# main.net
KiCad netlist of a schematic drawn in EAGLE
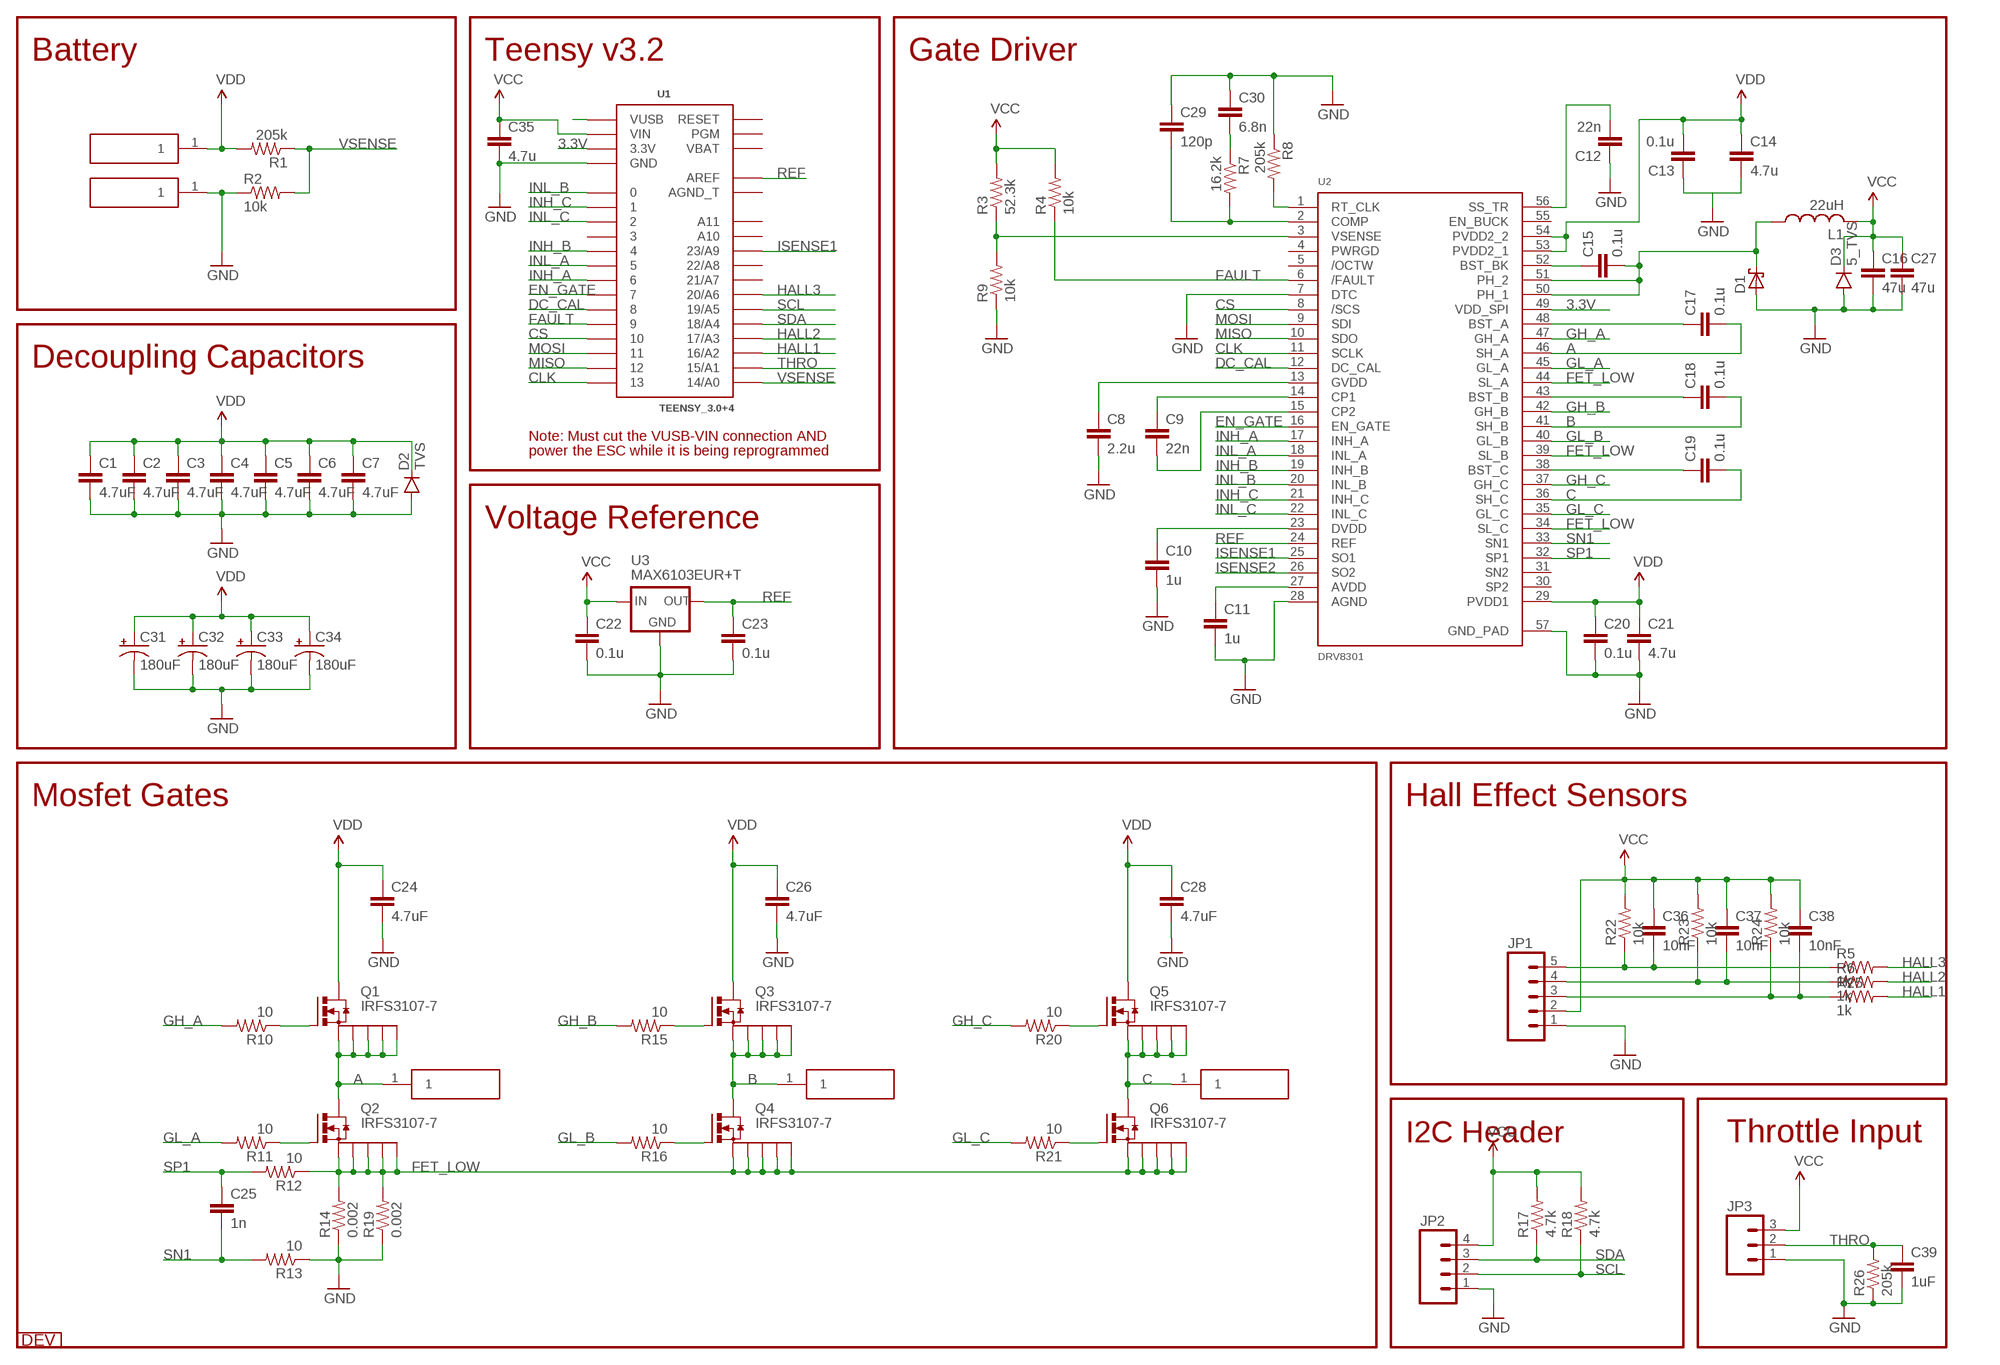
[diagram p0: schematic, sheet 1]

(export (version "E")
  (design (tool "Eeschema 10.0.6"))
  (components
    (comp (ref "C1")
      (value "4.7uF")
      (footprint "eagle-import:1206")
      (libsource (lib "eagle-import") (part "CAP1206"))
    )
    (comp (ref "C2")
      (value "4.7uF")
      (footprint "eagle-import:1206")
      (libsource (lib "eagle-import") (part "CAP1206"))
    )
    (comp (ref "C3")
      (value "4.7uF")
      (footprint "eagle-import:1206")
      (libsource (lib "eagle-import") (part "CAP1206"))
    )
    (comp (ref "C4")
      (value "4.7uF")
      (footprint "eagle-import:1206")
      (libsource (lib "eagle-import") (part "CAP1206"))
    )
    (comp (ref "C5")
      (value "4.7uF")
      (footprint "eagle-import:1206")
      (libsource (lib "eagle-import") (part "CAP1206"))
    )
    (comp (ref "C6")
      (value "4.7uF")
      (footprint "eagle-import:1206")
      (libsource (lib "eagle-import") (part "CAP1206"))
    )
    (comp (ref "C7")
      (value "4.7uF")
      (footprint "eagle-import:1206")
      (libsource (lib "eagle-import") (part "CAP1206"))
    )
    (comp (ref "C8")
      (value "2.2u")
      (footprint "eagle-import:0603-CAP")
      (libsource (lib "eagle-import") (part "CAP0603-CAP"))
    )
    (comp (ref "C9")
      (value "22n")
      (footprint "eagle-import:0603-CAP")
      (libsource (lib "eagle-import") (part "CAP0603-CAP"))
    )
    (comp (ref "C10")
      (value "1u")
      (footprint "eagle-import:0603-CAP")
      (libsource (lib "eagle-import") (part "CAP0603-CAP"))
    )
    (comp (ref "C11")
      (value "1u")
      (footprint "eagle-import:0603-CAP")
      (libsource (lib "eagle-import") (part "CAP0603-CAP"))
    )
    (comp (ref "C12")
      (value "22n")
      (footprint "eagle-import:0603-CAP")
      (libsource (lib "eagle-import") (part "CAP0603-CAP"))
    )
    (comp (ref "C13")
      (value "0.1u")
      (footprint "eagle-import:0603-CAP")
      (libsource (lib "eagle-import") (part "CAP0603-CAP"))
    )
    (comp (ref "C14")
      (value "4.7u")
      (footprint "eagle-import:0805")
      (libsource (lib "eagle-import") (part "CAP0805"))
    )
    (comp (ref "C15")
      (value "0.1u")
      (footprint "eagle-import:0603-CAP")
      (libsource (lib "eagle-import") (part "CAP0603-CAP"))
    )
    (comp (ref "C16")
      (value "47u")
      (footprint "eagle-import:0805")
      (libsource (lib "eagle-import") (part "CAP0805"))
    )
    (comp (ref "C17")
      (value "0.1u")
      (footprint "eagle-import:0603-CAP")
      (libsource (lib "eagle-import") (part "CAP0603-CAP"))
    )
    (comp (ref "C18")
      (value "0.1u")
      (footprint "eagle-import:0603-CAP")
      (libsource (lib "eagle-import") (part "CAP0603-CAP"))
    )
    (comp (ref "C19")
      (value "0.1u")
      (footprint "eagle-import:0603-CAP")
      (libsource (lib "eagle-import") (part "CAP0603-CAP"))
    )
    (comp (ref "C20")
      (value "0.1u")
      (footprint "eagle-import:0603-CAP")
      (libsource (lib "eagle-import") (part "CAP0603-CAP"))
    )
    (comp (ref "C21")
      (value "4.7u")
      (footprint "eagle-import:0805")
      (libsource (lib "eagle-import") (part "CAP0805"))
    )
    (comp (ref "C22")
      (value "0.1u")
      (footprint "eagle-import:0603-CAP")
      (libsource (lib "eagle-import") (part "CAP0603-CAP"))
    )
    (comp (ref "C23")
      (value "0.1u")
      (footprint "eagle-import:0603-CAP")
      (libsource (lib "eagle-import") (part "CAP0603-CAP"))
    )
    (comp (ref "C24")
      (value "4.7uF")
      (footprint "eagle-import:1206")
      (libsource (lib "eagle-import") (part "CAP1206"))
    )
    (comp (ref "C25")
      (value "1n")
      (footprint "eagle-import:0603-CAP")
      (libsource (lib "eagle-import") (part "CAP0603-CAP"))
    )
    (comp (ref "C26")
      (value "4.7uF")
      (footprint "eagle-import:1206")
      (libsource (lib "eagle-import") (part "CAP1206"))
    )
    (comp (ref "C27")
      (value "47u")
      (footprint "eagle-import:0805")
      (libsource (lib "eagle-import") (part "CAP0805"))
    )
    (comp (ref "C28")
      (value "4.7uF")
      (footprint "eagle-import:1206")
      (libsource (lib "eagle-import") (part "CAP1206"))
    )
    (comp (ref "C29")
      (value "120p")
      (footprint "eagle-import:0603-CAP")
      (libsource (lib "eagle-import") (part "CAP0603-CAP"))
    )
    (comp (ref "C30")
      (value "6.8n")
      (footprint "eagle-import:0603-CAP")
      (libsource (lib "eagle-import") (part "CAP0603-CAP"))
    )
    (comp (ref "C31")
      (value "180uF")
      (footprint "eagle-import:E3,5-8")
      (libsource (lib "eagle-import") (part "CPOL-USE3.5-8"))
    )
    (comp (ref "C32")
      (value "180uF")
      (footprint "eagle-import:E3,5-8")
      (libsource (lib "eagle-import") (part "CPOL-USE3.5-8"))
    )
    (comp (ref "C33")
      (value "180uF")
      (footprint "eagle-import:E3,5-8")
      (libsource (lib "eagle-import") (part "CPOL-USE3.5-8"))
    )
    (comp (ref "C34")
      (value "180uF")
      (footprint "eagle-import:E3,5-8")
      (libsource (lib "eagle-import") (part "CPOL-USE3.5-8"))
    )
    (comp (ref "C35")
      (value "4.7u")
      (footprint "eagle-import:0603-CAP")
      (libsource (lib "eagle-import") (part "CAP0603-CAP"))
    )
    (comp (ref "C36")
      (value "10nF")
      (footprint "eagle-import:0603-CAP")
      (libsource (lib "eagle-import") (part "SparkFun-Passives_CAP0603-CAP"))
    )
    (comp (ref "C37")
      (value "10nF")
      (footprint "eagle-import:0603-CAP")
      (libsource (lib "eagle-import") (part "SparkFun-Passives_CAP0603-CAP"))
    )
    (comp (ref "C38")
      (value "10nF")
      (footprint "eagle-import:0603-CAP")
      (libsource (lib "eagle-import") (part "SparkFun-Passives_CAP0603-CAP"))
    )
    (comp (ref "C39")
      (value "1uF")
      (footprint "eagle-import:0603-CAP")
      (libsource (lib "eagle-import") (part "SparkFun-Passives_CAP0603-CAP"))
    )
    (comp (ref "D1")
      (value "SCHOTTKY_SMA")
      (footprint "eagle-import:SMA")
      (libsource (lib "eagle-import") (part "SCHOTTKY_SMA"))
    )
    (comp (ref "D2")
      (value "TVS")
      (footprint "eagle-import:SMC")
      (libsource (lib "eagle-import") (part "DIODEES3J"))
    )
    (comp (ref "D3")
      (value "5_TVS")
      (footprint "eagle-import:SOT23-3")
      (libsource (lib "eagle-import") (part "DIODESOT23"))
    )
    (comp (ref "J1")
      (value "0.125_PAD")
      (footprint "eagle-import:0.125_PAD")
      (libsource (lib "eagle-import") (part "0.125_PAD"))
    )
    (comp (ref "J2")
      (value "0.125_PAD")
      (footprint "eagle-import:0.125_PAD")
      (libsource (lib "eagle-import") (part "0.125_PAD"))
    )
    (comp (ref "J3")
      (value "0.125_PAD")
      (footprint "eagle-import:0.125_PAD")
      (libsource (lib "eagle-import") (part "0.125_PAD"))
    )
    (comp (ref "J4")
      (value "0.125_PAD")
      (footprint "eagle-import:0.125_PAD")
      (libsource (lib "eagle-import") (part "0.125_PAD"))
    )
    (comp (ref "J5")
      (value "0.125_PAD")
      (footprint "eagle-import:0.125_PAD")
      (libsource (lib "eagle-import") (part "0.125_PAD"))
    )
    (comp (ref "JP1")
      (value "M05PTH")
      (footprint "eagle-import:1X05")
      (libsource (lib "eagle-import") (part "M05PTH"))
    )
    (comp (ref "JP2")
      (value "M04PTH")
      (footprint "eagle-import:1X04")
      (libsource (lib "eagle-import") (part "M04PTH"))
    )
    (comp (ref "JP3")
      (value "M03PTH")
      (footprint "eagle-import:1X03")
      (libsource (lib "eagle-import") (part "M03PTH"))
    )
    (comp (ref "L1")
      (value "22uH")
      (footprint "eagle-import:L5650M")
      (libsource (lib "eagle-import") (part "L-USL5650M"))
    )
    (comp (ref "Q1")
      (value "IRFS3107-7")
      (footprint "eagle-import:D2PAK-7")
      (libsource (lib "eagle-import") (part "IRFS3107-7"))
    )
    (comp (ref "Q2")
      (value "IRFS3107-7")
      (footprint "eagle-import:D2PAK-7")
      (libsource (lib "eagle-import") (part "IRFS3107-7"))
    )
    (comp (ref "Q3")
      (value "IRFS3107-7")
      (footprint "eagle-import:D2PAK-7")
      (libsource (lib "eagle-import") (part "IRFS3107-7"))
    )
    (comp (ref "Q4")
      (value "IRFS3107-7")
      (footprint "eagle-import:D2PAK-7")
      (libsource (lib "eagle-import") (part "IRFS3107-7"))
    )
    (comp (ref "Q5")
      (value "IRFS3107-7")
      (footprint "eagle-import:D2PAK-7")
      (libsource (lib "eagle-import") (part "IRFS3107-7"))
    )
    (comp (ref "Q6")
      (value "IRFS3107-7")
      (footprint "eagle-import:D2PAK-7")
      (libsource (lib "eagle-import") (part "IRFS3107-7"))
    )
    (comp (ref "R1")
      (value "205k")
      (footprint "eagle-import:0603-RES")
      (libsource (lib "eagle-import") (part "RESISTOR0603"))
    )
    (comp (ref "R2")
      (value "10k")
      (footprint "eagle-import:0603-RES")
      (libsource (lib "eagle-import") (part "RESISTOR0603"))
    )
    (comp (ref "R3")
      (value "52.3k")
      (footprint "eagle-import:0603-RES")
      (libsource (lib "eagle-import") (part "RESISTOR0603"))
    )
    (comp (ref "R4")
      (value "10k")
      (footprint "eagle-import:0603-RES")
      (libsource (lib "eagle-import") (part "RESISTOR0603"))
    )
    (comp (ref "R5")
      (value "1k")
      (footprint "eagle-import:0603-RES")
      (libsource (lib "eagle-import") (part "RESISTOR0603-RES"))
    )
    (comp (ref "R6")
      (value "1k")
      (footprint "eagle-import:0603-RES")
      (libsource (lib "eagle-import") (part "RESISTOR0603-RES"))
    )
    (comp (ref "R7")
      (value "16.2k")
      (footprint "eagle-import:0603-RES")
      (libsource (lib "eagle-import") (part "RESISTOR0603"))
    )
    (comp (ref "R8")
      (value "205k")
      (footprint "eagle-import:0603-RES")
      (libsource (lib "eagle-import") (part "RESISTOR0603"))
    )
    (comp (ref "R9")
      (value "10k")
      (footprint "eagle-import:0603-RES")
      (libsource (lib "eagle-import") (part "RESISTOR0603"))
    )
    (comp (ref "R10")
      (value "10")
      (footprint "eagle-import:0603-RES")
      (libsource (lib "eagle-import") (part "RESISTOR0603"))
    )
    (comp (ref "R11")
      (value "10")
      (footprint "eagle-import:0603-RES")
      (libsource (lib "eagle-import") (part "RESISTOR0603"))
    )
    (comp (ref "R12")
      (value "10")
      (footprint "eagle-import:0603-RES")
      (libsource (lib "eagle-import") (part "RESISTOR0603"))
    )
    (comp (ref "R13")
      (value "10")
      (footprint "eagle-import:0603-RES")
      (libsource (lib "eagle-import") (part "RESISTOR0603"))
    )
    (comp (ref "R14")
      (value "0.002")
      (footprint "eagle-import:R2512")
      (libsource (lib "eagle-import") (part "SparkFun-Resistors_RESISTOR2512"))
    )
    (comp (ref "R15")
      (value "10")
      (footprint "eagle-import:0603-RES")
      (libsource (lib "eagle-import") (part "RESISTOR0603"))
    )
    (comp (ref "R16")
      (value "10")
      (footprint "eagle-import:0603-RES")
      (libsource (lib "eagle-import") (part "RESISTOR0603"))
    )
    (comp (ref "R17")
      (value "4.7k")
      (footprint "eagle-import:0603-RES")
      (libsource (lib "eagle-import") (part "RESISTOR0603-RES"))
    )
    (comp (ref "R18")
      (value "4.7k")
      (footprint "eagle-import:0603-RES")
      (libsource (lib "eagle-import") (part "RESISTOR0603-RES"))
    )
    (comp (ref "R19")
      (value "0.002")
      (footprint "eagle-import:R2512")
      (libsource (lib "eagle-import") (part "SparkFun-Resistors_RESISTOR2512"))
    )
    (comp (ref "R20")
      (value "10")
      (footprint "eagle-import:0603-RES")
      (libsource (lib "eagle-import") (part "RESISTOR0603"))
    )
    (comp (ref "R21")
      (value "10")
      (footprint "eagle-import:0603-RES")
      (libsource (lib "eagle-import") (part "RESISTOR0603"))
    )
    (comp (ref "R22")
      (value "10k")
      (footprint "eagle-import:0603-RES")
      (libsource (lib "eagle-import") (part "RESISTOR0603"))
    )
    (comp (ref "R23")
      (value "10k")
      (footprint "eagle-import:0603-RES")
      (libsource (lib "eagle-import") (part "RESISTOR0603"))
    )
    (comp (ref "R24")
      (value "10k")
      (footprint "eagle-import:0603-RES")
      (libsource (lib "eagle-import") (part "RESISTOR0603"))
    )
    (comp (ref "R25")
      (value "1k")
      (footprint "eagle-import:0603-RES")
      (libsource (lib "eagle-import") (part "RESISTOR0603-RES"))
    )
    (comp (ref "R26")
      (value "205k")
      (footprint "eagle-import:0603-RES")
      (libsource (lib "eagle-import") (part "RESISTOR0603-RES"))
    )
    (comp (ref "U$16")
      (value "DEV")
      (footprint "eagle-import:DEV")
      (libsource (lib "eagle-import") (part "DEV"))
    )
    (comp (ref "U1")
      (value "TEENSY_3.0+4")
      (footprint "eagle-import:TEENSY_3.0+4")
      (libsource (lib "eagle-import") (part "TEENSY_3.0+4"))
    )
    (comp (ref "U2")
      (value "DRV8301")
      (footprint "eagle-import:DRV8301")
      (libsource (lib "eagle-import") (part "DRV8301"))
    )
    (comp (ref "U3")
      (value "MAX6103EUR+T")
      (footprint "eagle-import:SOT23-3")
      (libsource (lib "eagle-import") (part "MAX6103EUR+T"))
    )
  )
  (nets
    (net (code "1") (name "/3.3V") (class "Default")
      (node (ref "U1") (pin "3.3V") (pinfunction "3.3V_3.3V") (pintype "power_in"))
      (node (ref "U1") (pin "3.3V1") (pinfunction "3.3V_3.3V1") (pintype "power_in"))
      (node (ref "U2") (pin "49") (pinfunction "VDD_SPI_49") (pintype "bidirectional"))
    )
    (net (code "2") (name "/A") (class "Default")
      (node (ref "C17") (pin "2") (pinfunction "2_2") (pintype "passive"))
      (node (ref "J3") (pin "1") (pinfunction "1_1") (pintype "bidirectional"))
      (node (ref "Q1") (pin "S") (pinfunction "S_S") (pintype "passive"))
      (node (ref "Q1") (pin "S1") (pinfunction "S1_S1") (pintype "passive"))
      (node (ref "Q1") (pin "S2") (pinfunction "S2_S2") (pintype "passive"))
      (node (ref "Q1") (pin "S3") (pinfunction "S3_S3") (pintype "passive"))
      (node (ref "Q1") (pin "S4") (pinfunction "S4_S4") (pintype "passive"))
      (node (ref "Q2") (pin "D") (pinfunction "D_D") (pintype "passive"))
      (node (ref "U2") (pin "46") (pinfunction "SH_A_46") (pintype "bidirectional"))
    )
    (net (code "3") (name "/AGND_T") (class "Default")
      (node (ref "U1") (pin "AGND_T") (pinfunction "AGND_T_AGND_T") (pintype "power_in"))
    )
    (net (code "4") (name "/B") (class "Default")
      (node (ref "C18") (pin "2") (pinfunction "2_2") (pintype "passive"))
      (node (ref "J4") (pin "1") (pinfunction "1_1") (pintype "bidirectional"))
      (node (ref "Q3") (pin "S") (pinfunction "S_S") (pintype "passive"))
      (node (ref "Q3") (pin "S1") (pinfunction "S1_S1") (pintype "passive"))
      (node (ref "Q3") (pin "S2") (pinfunction "S2_S2") (pintype "passive"))
      (node (ref "Q3") (pin "S3") (pinfunction "S3_S3") (pintype "passive"))
      (node (ref "Q3") (pin "S4") (pinfunction "S4_S4") (pintype "passive"))
      (node (ref "Q4") (pin "D") (pinfunction "D_D") (pintype "passive"))
      (node (ref "U2") (pin "41") (pinfunction "SH_B_41") (pintype "bidirectional"))
    )
    (net (code "5") (name "/C") (class "Default")
      (node (ref "C19") (pin "2") (pinfunction "2_2") (pintype "passive"))
      (node (ref "J5") (pin "1") (pinfunction "1_1") (pintype "bidirectional"))
      (node (ref "Q5") (pin "S") (pinfunction "S_S") (pintype "passive"))
      (node (ref "Q5") (pin "S1") (pinfunction "S1_S1") (pintype "passive"))
      (node (ref "Q5") (pin "S2") (pinfunction "S2_S2") (pintype "passive"))
      (node (ref "Q5") (pin "S3") (pinfunction "S3_S3") (pintype "passive"))
      (node (ref "Q5") (pin "S4") (pinfunction "S4_S4") (pintype "passive"))
      (node (ref "Q6") (pin "D") (pinfunction "D_D") (pintype "passive"))
      (node (ref "U2") (pin "36") (pinfunction "SH_C_36") (pintype "bidirectional"))
    )
    (net (code "6") (name "/CLK") (class "Default")
      (node (ref "U1") (pin "13") (pinfunction "13_13") (pintype "bidirectional"))
      (node (ref "U2") (pin "11") (pinfunction "SCLK_11") (pintype "bidirectional"))
    )
    (net (code "7") (name "/CS") (class "Default")
      (node (ref "U1") (pin "10") (pinfunction "10_10") (pintype "bidirectional"))
      (node (ref "U2") (pin "8") (pinfunction "/SCS_8") (pintype "bidirectional"))
    )
    (net (code "8") (name "/DC_CAL") (class "Default")
      (node (ref "U1") (pin "8") (pinfunction "8_8") (pintype "bidirectional"))
      (node (ref "U2") (pin "12") (pinfunction "DC_CAL_12") (pintype "bidirectional"))
    )
    (net (code "9") (name "/EN_GATE") (class "Default")
      (node (ref "U1") (pin "7") (pinfunction "7_7") (pintype "bidirectional"))
      (node (ref "U2") (pin "16") (pinfunction "EN_GATE_16") (pintype "bidirectional"))
    )
    (net (code "10") (name "/FAULT") (class "Default")
      (node (ref "R4") (pin "1") (pinfunction "1_1") (pintype "passive"))
      (node (ref "U1") (pin "9") (pinfunction "9_9") (pintype "bidirectional"))
      (node (ref "U2") (pin "6") (pinfunction "/FAULT_6") (pintype "bidirectional"))
    )
    (net (code "11") (name "/FET_LOW") (class "Default")
      (node (ref "Q2") (pin "S") (pinfunction "S_S") (pintype "passive"))
      (node (ref "Q2") (pin "S1") (pinfunction "S1_S1") (pintype "passive"))
      (node (ref "Q2") (pin "S2") (pinfunction "S2_S2") (pintype "passive"))
      (node (ref "Q2") (pin "S3") (pinfunction "S3_S3") (pintype "passive"))
      (node (ref "Q2") (pin "S4") (pinfunction "S4_S4") (pintype "passive"))
      (node (ref "Q4") (pin "S") (pinfunction "S_S") (pintype "passive"))
      (node (ref "Q4") (pin "S1") (pinfunction "S1_S1") (pintype "passive"))
      (node (ref "Q4") (pin "S2") (pinfunction "S2_S2") (pintype "passive"))
      (node (ref "Q4") (pin "S3") (pinfunction "S3_S3") (pintype "passive"))
      (node (ref "Q4") (pin "S4") (pinfunction "S4_S4") (pintype "passive"))
      (node (ref "Q6") (pin "S") (pinfunction "S_S") (pintype "passive"))
      (node (ref "Q6") (pin "S1") (pinfunction "S1_S1") (pintype "passive"))
      (node (ref "Q6") (pin "S2") (pinfunction "S2_S2") (pintype "passive"))
      (node (ref "Q6") (pin "S3") (pinfunction "S3_S3") (pintype "passive"))
      (node (ref "Q6") (pin "S4") (pinfunction "S4_S4") (pintype "passive"))
      (node (ref "R12") (pin "1") (pinfunction "1_1") (pintype "passive"))
      (node (ref "R14") (pin "2") (pinfunction "2_2") (pintype "passive"))
      (node (ref "R19") (pin "2") (pinfunction "2_2") (pintype "passive"))
      (node (ref "U2") (pin "34") (pinfunction "SL_C_34") (pintype "bidirectional"))
      (node (ref "U2") (pin "39") (pinfunction "SL_B_39") (pintype "bidirectional"))
      (node (ref "U2") (pin "44") (pinfunction "SL_A_44") (pintype "bidirectional"))
    )
    (net (code "12") (name "/GH_A") (class "Default")
      (node (ref "R10") (pin "2") (pinfunction "2_2") (pintype "passive"))
      (node (ref "U2") (pin "47") (pinfunction "GH_A_47") (pintype "bidirectional"))
    )
    (net (code "13") (name "/GH_B") (class "Default")
      (node (ref "R15") (pin "2") (pinfunction "2_2") (pintype "passive"))
      (node (ref "U2") (pin "42") (pinfunction "GH_B_42") (pintype "bidirectional"))
    )
    (net (code "14") (name "/GH_C") (class "Default")
      (node (ref "R20") (pin "2") (pinfunction "2_2") (pintype "passive"))
      (node (ref "U2") (pin "37") (pinfunction "GH_C_37") (pintype "bidirectional"))
    )
    (net (code "15") (name "/GL_A") (class "Default")
      (node (ref "R11") (pin "2") (pinfunction "2_2") (pintype "passive"))
      (node (ref "U2") (pin "45") (pinfunction "GL_A_45") (pintype "bidirectional"))
    )
    (net (code "16") (name "/GL_B") (class "Default")
      (node (ref "R16") (pin "2") (pinfunction "2_2") (pintype "passive"))
      (node (ref "U2") (pin "40") (pinfunction "GL_B_40") (pintype "bidirectional"))
    )
    (net (code "17") (name "/GL_C") (class "Default")
      (node (ref "R21") (pin "2") (pinfunction "2_2") (pintype "passive"))
      (node (ref "U2") (pin "35") (pinfunction "GL_C_35") (pintype "bidirectional"))
    )
    (net (code "18") (name "/HALL1") (class "Default")
      (node (ref "R25") (pin "2") (pinfunction "2_2") (pintype "passive"))
      (node (ref "U1") (pin "16/A2") (pinfunction "16/A2_16/A2") (pintype "bidirectional"))
    )
    (net (code "19") (name "/HALL2") (class "Default")
      (node (ref "R6") (pin "2") (pinfunction "2_2") (pintype "passive"))
      (node (ref "U1") (pin "17/A3") (pinfunction "17/A3_17/A3") (pintype "bidirectional"))
    )
    (net (code "20") (name "/HALL3") (class "Default")
      (node (ref "R5") (pin "2") (pinfunction "2_2") (pintype "passive"))
      (node (ref "U1") (pin "20/A6") (pinfunction "20/A6_20/A6") (pintype "bidirectional"))
    )
    (net (code "21") (name "/INH_A") (class "Default")
      (node (ref "U1") (pin "6") (pinfunction "6_6") (pintype "bidirectional"))
      (node (ref "U2") (pin "17") (pinfunction "INH_A_17") (pintype "bidirectional"))
    )
    (net (code "22") (name "/INH_B") (class "Default")
      (node (ref "U1") (pin "4") (pinfunction "4_4") (pintype "bidirectional"))
      (node (ref "U2") (pin "19") (pinfunction "INH_B_19") (pintype "bidirectional"))
    )
    (net (code "23") (name "/INH_C") (class "Default")
      (node (ref "U1") (pin "1") (pinfunction "1_1") (pintype "bidirectional"))
      (node (ref "U2") (pin "21") (pinfunction "INH_C_21") (pintype "bidirectional"))
    )
    (net (code "24") (name "/INL_A") (class "Default")
      (node (ref "U1") (pin "5") (pinfunction "5_5") (pintype "bidirectional"))
      (node (ref "U2") (pin "18") (pinfunction "INL_A_18") (pintype "bidirectional"))
    )
    (net (code "25") (name "/INL_B") (class "Default")
      (node (ref "U1") (pin "0") (pinfunction "0_0") (pintype "bidirectional"))
      (node (ref "U2") (pin "20") (pinfunction "INL_B_20") (pintype "bidirectional"))
    )
    (net (code "26") (name "/INL_C") (class "Default")
      (node (ref "U1") (pin "2") (pinfunction "2_2") (pintype "bidirectional"))
      (node (ref "U2") (pin "22") (pinfunction "INL_C_22") (pintype "bidirectional"))
    )
    (net (code "27") (name "/ISENSE1") (class "Default")
      (node (ref "U1") (pin "23/A9") (pinfunction "23/A9_23/A9") (pintype "bidirectional"))
      (node (ref "U2") (pin "25") (pinfunction "SO1_25") (pintype "bidirectional"))
    )
    (net (code "28") (name "/ISENSE2") (class "Default")
      (node (ref "U2") (pin "26") (pinfunction "SO2_26") (pintype "bidirectional"))
    )
    (net (code "29") (name "/MISO") (class "Default")
      (node (ref "U1") (pin "12") (pinfunction "12_12") (pintype "bidirectional"))
      (node (ref "U2") (pin "10") (pinfunction "SDO_10") (pintype "bidirectional"))
    )
    (net (code "30") (name "/MOSI") (class "Default")
      (node (ref "U1") (pin "11") (pinfunction "11_11") (pintype "bidirectional"))
      (node (ref "U2") (pin "9") (pinfunction "SDI_9") (pintype "bidirectional"))
    )
    (net (code "31") (name "/REF") (class "Default")
      (node (ref "C23") (pin "1") (pinfunction "1_1") (pintype "passive"))
      (node (ref "U1") (pin "AREF") (pinfunction "AREF_AREF") (pintype "power_in"))
      (node (ref "U2") (pin "24") (pinfunction "REF_24") (pintype "bidirectional"))
      (node (ref "U3") (pin "2") (pinfunction "OUT_2") (pintype "output"))
    )
    (net (code "32") (name "/SCL") (class "Default")
      (node (ref "JP2") (pin "2") (pinfunction "2_2") (pintype "passive"))
      (node (ref "R18") (pin "1") (pinfunction "1_1") (pintype "passive"))
      (node (ref "U1") (pin "19/A5") (pinfunction "19/A5_19/A5") (pintype "bidirectional"))
    )
    (net (code "33") (name "/SDA") (class "Default")
      (node (ref "JP2") (pin "3") (pinfunction "3_3") (pintype "passive"))
      (node (ref "R17") (pin "1") (pinfunction "1_1") (pintype "passive"))
      (node (ref "U1") (pin "18/A4") (pinfunction "18/A4_18/A4") (pintype "bidirectional"))
    )
    (net (code "34") (name "/SN1") (class "Default")
      (node (ref "C25") (pin "2") (pinfunction "2_2") (pintype "passive"))
      (node (ref "R13") (pin "2") (pinfunction "2_2") (pintype "passive"))
      (node (ref "U2") (pin "33") (pinfunction "SN1_33") (pintype "bidirectional"))
    )
    (net (code "35") (name "/SP1") (class "Default")
      (node (ref "C25") (pin "1") (pinfunction "1_1") (pintype "passive"))
      (node (ref "R12") (pin "2") (pinfunction "2_2") (pintype "passive"))
      (node (ref "U2") (pin "32") (pinfunction "SP1_32") (pintype "bidirectional"))
    )
    (net (code "36") (name "/THRO") (class "Default")
      (node (ref "C39") (pin "1") (pinfunction "1_1") (pintype "passive"))
      (node (ref "JP3") (pin "2") (pinfunction "2_2") (pintype "passive"))
      (node (ref "R26") (pin "2") (pinfunction "2_2") (pintype "passive"))
      (node (ref "U1") (pin "15/A1") (pinfunction "15/A1_15/A1") (pintype "bidirectional"))
    )
    (net (code "37") (name "/VBAT") (class "Default")
      (node (ref "U1") (pin "VBAT") (pinfunction "VBAT_VBAT") (pintype "power_in"))
    )
    (net (code "38") (name "/VSENSE") (class "Default")
      (node (ref "R1") (pin "1") (pinfunction "1_1") (pintype "passive"))
      (node (ref "R2") (pin "2") (pinfunction "2_2") (pintype "passive"))
      (node (ref "U1") (pin "14/A0") (pinfunction "14/A0_14/A0") (pintype "bidirectional"))
    )
    (net (code "39") (name "GND") (class "Default")
      (node (ref "C1") (pin "2") (pinfunction "2_2") (pintype "passive"))
      (node (ref "C10") (pin "2") (pinfunction "2_2") (pintype "passive"))
      (node (ref "C11") (pin "2") (pinfunction "2_2") (pintype "passive"))
      (node (ref "C12") (pin "1") (pinfunction "1_1") (pintype "passive"))
      (node (ref "C13") (pin "1") (pinfunction "1_1") (pintype "passive"))
      (node (ref "C14") (pin "2") (pinfunction "2_2") (pintype "passive"))
      (node (ref "C16") (pin "2") (pinfunction "2_2") (pintype "passive"))
      (node (ref "C2") (pin "2") (pinfunction "2_2") (pintype "passive"))
      (node (ref "C20") (pin "2") (pinfunction "2_2") (pintype "passive"))
      (node (ref "C21") (pin "2") (pinfunction "2_2") (pintype "passive"))
      (node (ref "C22") (pin "2") (pinfunction "2_2") (pintype "passive"))
      (node (ref "C23") (pin "2") (pinfunction "2_2") (pintype "passive"))
      (node (ref "C24") (pin "2") (pinfunction "2_2") (pintype "passive"))
      (node (ref "C26") (pin "2") (pinfunction "2_2") (pintype "passive"))
      (node (ref "C27") (pin "2") (pinfunction "2_2") (pintype "passive"))
      (node (ref "C28") (pin "2") (pinfunction "2_2") (pintype "passive"))
      (node (ref "C29") (pin "1") (pinfunction "1_1") (pintype "passive"))
      (node (ref "C3") (pin "2") (pinfunction "2_2") (pintype "passive"))
      (node (ref "C30") (pin "1") (pinfunction "1_1") (pintype "passive"))
      (node (ref "C31") (pin "-") (pinfunction "-_-") (pintype "passive"))
      (node (ref "C32") (pin "-") (pinfunction "-_-") (pintype "passive"))
      (node (ref "C33") (pin "-") (pinfunction "-_-") (pintype "passive"))
      (node (ref "C34") (pin "-") (pinfunction "-_-") (pintype "passive"))
      (node (ref "C35") (pin "2") (pinfunction "2_2") (pintype "passive"))
      (node (ref "C39") (pin "2") (pinfunction "2_2") (pintype "passive"))
      (node (ref "C4") (pin "2") (pinfunction "2_2") (pintype "passive"))
      (node (ref "C5") (pin "2") (pinfunction "2_2") (pintype "passive"))
      (node (ref "C6") (pin "2") (pinfunction "2_2") (pintype "passive"))
      (node (ref "C7") (pin "2") (pinfunction "2_2") (pintype "passive"))
      (node (ref "C8") (pin "2") (pinfunction "2_2") (pintype "passive"))
      (node (ref "D1") (pin "A") (pinfunction "A_A") (pintype "passive"))
      (node (ref "D2") (pin "A") (pinfunction "A_A") (pintype "passive"))
      (node (ref "D3") (pin "1") (pinfunction "A_1") (pintype "passive"))
      (node (ref "J2") (pin "1") (pinfunction "1_1") (pintype "bidirectional"))
      (node (ref "JP1") (pin "1") (pinfunction "1_1") (pintype "passive"))
      (node (ref "JP2") (pin "1") (pinfunction "1_1") (pintype "passive"))
      (node (ref "JP3") (pin "1") (pinfunction "1_1") (pintype "passive"))
      (node (ref "R13") (pin "1") (pinfunction "1_1") (pintype "passive"))
      (node (ref "R14") (pin "1") (pinfunction "1_1") (pintype "passive"))
      (node (ref "R19") (pin "1") (pinfunction "1_1") (pintype "passive"))
      (node (ref "R2") (pin "1") (pinfunction "1_1") (pintype "passive"))
      (node (ref "R26") (pin "1") (pinfunction "1_1") (pintype "passive"))
      (node (ref "R8") (pin "1") (pinfunction "1_1") (pintype "passive"))
      (node (ref "R9") (pin "1") (pinfunction "1_1") (pintype "passive"))
      (node (ref "U1") (pin "GND") (pinfunction "GND_GND") (pintype "power_in"))
      (node (ref "U1") (pin "GND1") (pinfunction "GND_GND1") (pintype "power_in"))
      (node (ref "U2") (pin "28") (pinfunction "AGND_28") (pintype "bidirectional"))
      (node (ref "U2") (pin "57") (pinfunction "GND_PAD_57") (pintype "bidirectional"))
      (node (ref "U2") (pin "7") (pinfunction "DTC_7") (pintype "bidirectional"))
      (node (ref "U3") (pin "3") (pinfunction "GND_3") (pintype "input"))
    )
    (net (code "40") (name "Net-(C30-Pad2)") (class "Default")
      (node (ref "C30") (pin "2") (pinfunction "2_2") (pintype "passive"))
      (node (ref "R7") (pin "1") (pinfunction "1_1") (pintype "passive"))
    )
    (net (code "41") (name "Net-(C36-Pad2)") (class "Default")
      (node (ref "C36") (pin "2") (pinfunction "2_2") (pintype "passive"))
      (node (ref "JP1") (pin "5") (pinfunction "5_5") (pintype "passive"))
      (node (ref "R22") (pin "1") (pinfunction "1_1") (pintype "passive"))
      (node (ref "R5") (pin "1") (pinfunction "1_1") (pintype "passive"))
    )
    (net (code "42") (name "Net-(C37-Pad2)") (class "Default")
      (node (ref "C37") (pin "2") (pinfunction "2_2") (pintype "passive"))
      (node (ref "JP1") (pin "4") (pinfunction "4_4") (pintype "passive"))
      (node (ref "R23") (pin "1") (pinfunction "1_1") (pintype "passive"))
      (node (ref "R6") (pin "1") (pinfunction "1_1") (pintype "passive"))
    )
    (net (code "43") (name "Net-(C38-Pad2)") (class "Default")
      (node (ref "C38") (pin "2") (pinfunction "2_2") (pintype "passive"))
      (node (ref "JP1") (pin "3") (pinfunction "3_3") (pintype "passive"))
      (node (ref "R24") (pin "1") (pinfunction "1_1") (pintype "passive"))
      (node (ref "R25") (pin "1") (pinfunction "1_1") (pintype "passive"))
    )
    (net (code "44") (name "Net-(Q1-PadG)") (class "Default")
      (node (ref "Q1") (pin "G") (pinfunction "G_G") (pintype "passive"))
      (node (ref "R10") (pin "1") (pinfunction "1_1") (pintype "passive"))
    )
    (net (code "45") (name "Net-(Q2-PadG)") (class "Default")
      (node (ref "Q2") (pin "G") (pinfunction "G_G") (pintype "passive"))
      (node (ref "R11") (pin "1") (pinfunction "1_1") (pintype "passive"))
    )
    (net (code "46") (name "Net-(Q3-PadG)") (class "Default")
      (node (ref "Q3") (pin "G") (pinfunction "G_G") (pintype "passive"))
      (node (ref "R15") (pin "1") (pinfunction "1_1") (pintype "passive"))
    )
    (net (code "47") (name "Net-(Q4-PadG)") (class "Default")
      (node (ref "Q4") (pin "G") (pinfunction "G_G") (pintype "passive"))
      (node (ref "R16") (pin "1") (pinfunction "1_1") (pintype "passive"))
    )
    (net (code "48") (name "Net-(Q5-PadG)") (class "Default")
      (node (ref "Q5") (pin "G") (pinfunction "G_G") (pintype "passive"))
      (node (ref "R20") (pin "1") (pinfunction "1_1") (pintype "passive"))
    )
    (net (code "49") (name "Net-(Q6-PadG)") (class "Default")
      (node (ref "Q6") (pin "G") (pinfunction "G_G") (pintype "passive"))
      (node (ref "R21") (pin "1") (pinfunction "1_1") (pintype "passive"))
    )
    (net (code "50") (name "Net-(U2-AVDD)") (class "Default")
      (node (ref "C11") (pin "1") (pinfunction "1_1") (pintype "passive"))
      (node (ref "U2") (pin "27") (pinfunction "AVDD_27") (pintype "bidirectional"))
    )
    (net (code "51") (name "Net-(U2-BST_A)") (class "Default")
      (node (ref "C17") (pin "1") (pinfunction "1_1") (pintype "passive"))
      (node (ref "U2") (pin "48") (pinfunction "BST_A_48") (pintype "bidirectional"))
    )
    (net (code "52") (name "Net-(U2-BST_B)") (class "Default")
      (node (ref "C18") (pin "1") (pinfunction "1_1") (pintype "passive"))
      (node (ref "U2") (pin "43") (pinfunction "BST_B_43") (pintype "bidirectional"))
    )
    (net (code "53") (name "Net-(U2-BST_BK)") (class "Default")
      (node (ref "C15") (pin "1") (pinfunction "1_1") (pintype "passive"))
      (node (ref "U2") (pin "52") (pinfunction "BST_BK_52") (pintype "bidirectional"))
    )
    (net (code "54") (name "Net-(U2-BST_C)") (class "Default")
      (node (ref "C19") (pin "1") (pinfunction "1_1") (pintype "passive"))
      (node (ref "U2") (pin "38") (pinfunction "BST_C_38") (pintype "bidirectional"))
    )
    (net (code "55") (name "Net-(U2-COMP)") (class "Default")
      (node (ref "C29") (pin "2") (pinfunction "2_2") (pintype "passive"))
      (node (ref "R7") (pin "2") (pinfunction "2_2") (pintype "passive"))
      (node (ref "U2") (pin "2") (pinfunction "COMP_2") (pintype "bidirectional"))
    )
    (net (code "56") (name "Net-(U2-CP1)") (class "Default")
      (node (ref "C9") (pin "1") (pinfunction "1_1") (pintype "passive"))
      (node (ref "U2") (pin "14") (pinfunction "CP1_14") (pintype "bidirectional"))
    )
    (net (code "57") (name "Net-(U2-CP2)") (class "Default")
      (node (ref "C9") (pin "2") (pinfunction "2_2") (pintype "passive"))
      (node (ref "U2") (pin "15") (pinfunction "CP2_15") (pintype "bidirectional"))
    )
    (net (code "58") (name "Net-(U2-DVDD)") (class "Default")
      (node (ref "C10") (pin "1") (pinfunction "1_1") (pintype "passive"))
      (node (ref "U2") (pin "23") (pinfunction "DVDD_23") (pintype "bidirectional"))
    )
    (net (code "59") (name "Net-(U2-GVDD)") (class "Default")
      (node (ref "C8") (pin "1") (pinfunction "1_1") (pintype "passive"))
      (node (ref "U2") (pin "13") (pinfunction "GVDD_13") (pintype "bidirectional"))
    )
    (net (code "60") (name "Net-(U2-PH_1)") (class "Default")
      (node (ref "C15") (pin "2") (pinfunction "2_2") (pintype "passive"))
      (node (ref "D1") (pin "C") (pinfunction "C_C") (pintype "passive"))
      (node (ref "L1") (pin "1") (pinfunction "1_1") (pintype "passive"))
      (node (ref "U2") (pin "50") (pinfunction "PH_1_50") (pintype "bidirectional"))
      (node (ref "U2") (pin "51") (pinfunction "PH_2_51") (pintype "bidirectional"))
    )
    (net (code "61") (name "Net-(U2-RT_CLK)") (class "Default")
      (node (ref "R8") (pin "2") (pinfunction "2_2") (pintype "passive"))
      (node (ref "U2") (pin "1") (pinfunction "RT_CLK_1") (pintype "bidirectional"))
    )
    (net (code "62") (name "Net-(U2-SS_TR)") (class "Default")
      (node (ref "C12") (pin "2") (pinfunction "2_2") (pintype "passive"))
      (node (ref "U2") (pin "56") (pinfunction "SS_TR_56") (pintype "bidirectional"))
    )
    (net (code "63") (name "Net-(U2-VSENSE)") (class "Default")
      (node (ref "R3") (pin "1") (pinfunction "1_1") (pintype "passive"))
      (node (ref "R9") (pin "2") (pinfunction "2_2") (pintype "passive"))
      (node (ref "U2") (pin "3") (pinfunction "VSENSE_3") (pintype "bidirectional"))
    )
    (net (code "64") (name "VCC") (class "Default")
      (node (ref "C16") (pin "1") (pinfunction "1_1") (pintype "passive"))
      (node (ref "C22") (pin "1") (pinfunction "1_1") (pintype "passive"))
      (node (ref "C27") (pin "1") (pinfunction "1_1") (pintype "passive"))
      (node (ref "C35") (pin "1") (pinfunction "1_1") (pintype "passive"))
      (node (ref "C36") (pin "1") (pinfunction "1_1") (pintype "passive"))
      (node (ref "C37") (pin "1") (pinfunction "1_1") (pintype "passive"))
      (node (ref "C38") (pin "1") (pinfunction "1_1") (pintype "passive"))
      (node (ref "D3") (pin "3") (pinfunction "C_3") (pintype "passive"))
      (node (ref "JP1") (pin "2") (pinfunction "2_2") (pintype "passive"))
      (node (ref "JP2") (pin "4") (pinfunction "4_4") (pintype "passive"))
      (node (ref "JP3") (pin "3") (pinfunction "3_3") (pintype "passive"))
      (node (ref "L1") (pin "2") (pinfunction "2_2") (pintype "passive"))
      (node (ref "R17") (pin "2") (pinfunction "2_2") (pintype "passive"))
      (node (ref "R18") (pin "2") (pinfunction "2_2") (pintype "passive"))
      (node (ref "R22") (pin "2") (pinfunction "2_2") (pintype "passive"))
      (node (ref "R23") (pin "2") (pinfunction "2_2") (pintype "passive"))
      (node (ref "R24") (pin "2") (pinfunction "2_2") (pintype "passive"))
      (node (ref "R3") (pin "2") (pinfunction "2_2") (pintype "passive"))
      (node (ref "R4") (pin "2") (pinfunction "2_2") (pintype "passive"))
      (node (ref "U1") (pin "VIN") (pinfunction "VIN_VIN") (pintype "power_in"))
      (node (ref "U3") (pin "1") (pinfunction "IN_1") (pintype "input"))
    )
    (net (code "65") (name "VDD") (class "Default")
      (node (ref "C1") (pin "1") (pinfunction "1_1") (pintype "passive"))
      (node (ref "C13") (pin "2") (pinfunction "2_2") (pintype "passive"))
      (node (ref "C14") (pin "1") (pinfunction "1_1") (pintype "passive"))
      (node (ref "C2") (pin "1") (pinfunction "1_1") (pintype "passive"))
      (node (ref "C20") (pin "1") (pinfunction "1_1") (pintype "passive"))
      (node (ref "C21") (pin "1") (pinfunction "1_1") (pintype "passive"))
      (node (ref "C24") (pin "1") (pinfunction "1_1") (pintype "passive"))
      (node (ref "C26") (pin "1") (pinfunction "1_1") (pintype "passive"))
      (node (ref "C28") (pin "1") (pinfunction "1_1") (pintype "passive"))
      (node (ref "C3") (pin "1") (pinfunction "1_1") (pintype "passive"))
      (node (ref "C31") (pin "+") (pinfunction "+_+") (pintype "passive"))
      (node (ref "C32") (pin "+") (pinfunction "+_+") (pintype "passive"))
      (node (ref "C33") (pin "+") (pinfunction "+_+") (pintype "passive"))
      (node (ref "C34") (pin "+") (pinfunction "+_+") (pintype "passive"))
      (node (ref "C4") (pin "1") (pinfunction "1_1") (pintype "passive"))
      (node (ref "C5") (pin "1") (pinfunction "1_1") (pintype "passive"))
      (node (ref "C6") (pin "1") (pinfunction "1_1") (pintype "passive"))
      (node (ref "C7") (pin "1") (pinfunction "1_1") (pintype "passive"))
      (node (ref "D2") (pin "C") (pinfunction "C_C") (pintype "passive"))
      (node (ref "J1") (pin "1") (pinfunction "1_1") (pintype "bidirectional"))
      (node (ref "Q1") (pin "D") (pinfunction "D_D") (pintype "passive"))
      (node (ref "Q3") (pin "D") (pinfunction "D_D") (pintype "passive"))
      (node (ref "Q5") (pin "D") (pinfunction "D_D") (pintype "passive"))
      (node (ref "R1") (pin "2") (pinfunction "2_2") (pintype "passive"))
      (node (ref "U2") (pin "29") (pinfunction "PVDD1_29") (pintype "bidirectional"))
      (node (ref "U2") (pin "53") (pinfunction "PVDD2_1_53") (pintype "bidirectional"))
      (node (ref "U2") (pin "54") (pinfunction "PVDD2_2_54") (pintype "bidirectional"))
    )
    (net (code "66") (name "unconnected-(U1-Pad3)") (class "Default")
      (node (ref "U1") (pin "3") (pinfunction "3_3") (pintype "bidirectional"))
    )
    (net (code "67") (name "unconnected-(U1-Pad21{slash}A7)") (class "Default")
      (node (ref "U1") (pin "21/A7") (pinfunction "21/A7_21/A7") (pintype "bidirectional"))
    )
    (net (code "68") (name "unconnected-(U1-Pad22{slash}A8)") (class "Default")
      (node (ref "U1") (pin "22/A8") (pinfunction "22/A8_22/A8") (pintype "bidirectional"))
    )
    (net (code "69") (name "unconnected-(U1-PadA10)") (class "Default")
      (node (ref "U1") (pin "A10") (pinfunction "A10_A10") (pintype "bidirectional"))
    )
    (net (code "70") (name "unconnected-(U1-PadA11)") (class "Default")
      (node (ref "U1") (pin "A11") (pinfunction "A11_A11") (pintype "bidirectional"))
    )
    (net (code "71") (name "unconnected-(U1-PadPGM)") (class "Default")
      (node (ref "U1") (pin "PGM") (pinfunction "PGM_PGM") (pintype "bidirectional"))
    )
    (net (code "72") (name "unconnected-(U1-PadRESET)") (class "Default")
      (node (ref "U1") (pin "RESET") (pinfunction "RESET_RESET") (pintype "bidirectional"))
    )
    (net (code "73") (name "unconnected-(U1-PadVUSB)") (class "Default")
      (node (ref "U1") (pin "VUSB") (pinfunction "VUSB_VUSB") (pintype "power_in"))
    )
    (net (code "74") (name "unconnected-(U2-EN_BUCK-Pad55)") (class "Default")
      (node (ref "U2") (pin "55") (pinfunction "EN_BUCK_55") (pintype "bidirectional"))
    )
    (net (code "75") (name "unconnected-(U2-PWRGD-Pad4)") (class "Default")
      (node (ref "U2") (pin "4") (pinfunction "PWRGD_4") (pintype "bidirectional"))
    )
    (net (code "76") (name "unconnected-(U2-SN2-Pad31)") (class "Default")
      (node (ref "U2") (pin "31") (pinfunction "SN2_31") (pintype "bidirectional"))
    )
    (net (code "77") (name "unconnected-(U2-SP2-Pad30)") (class "Default")
      (node (ref "U2") (pin "30") (pinfunction "SP2_30") (pintype "bidirectional"))
    )
    (net (code "78") (name "unconnected-(U2-{slash}OCTW-Pad5)") (class "Default")
      (node (ref "U2") (pin "5") (pinfunction "/OCTW_5") (pintype "bidirectional"))
    )
  )
)
